# DK_ESC.net
KiCad netlist of a schematic drawn in EAGLE
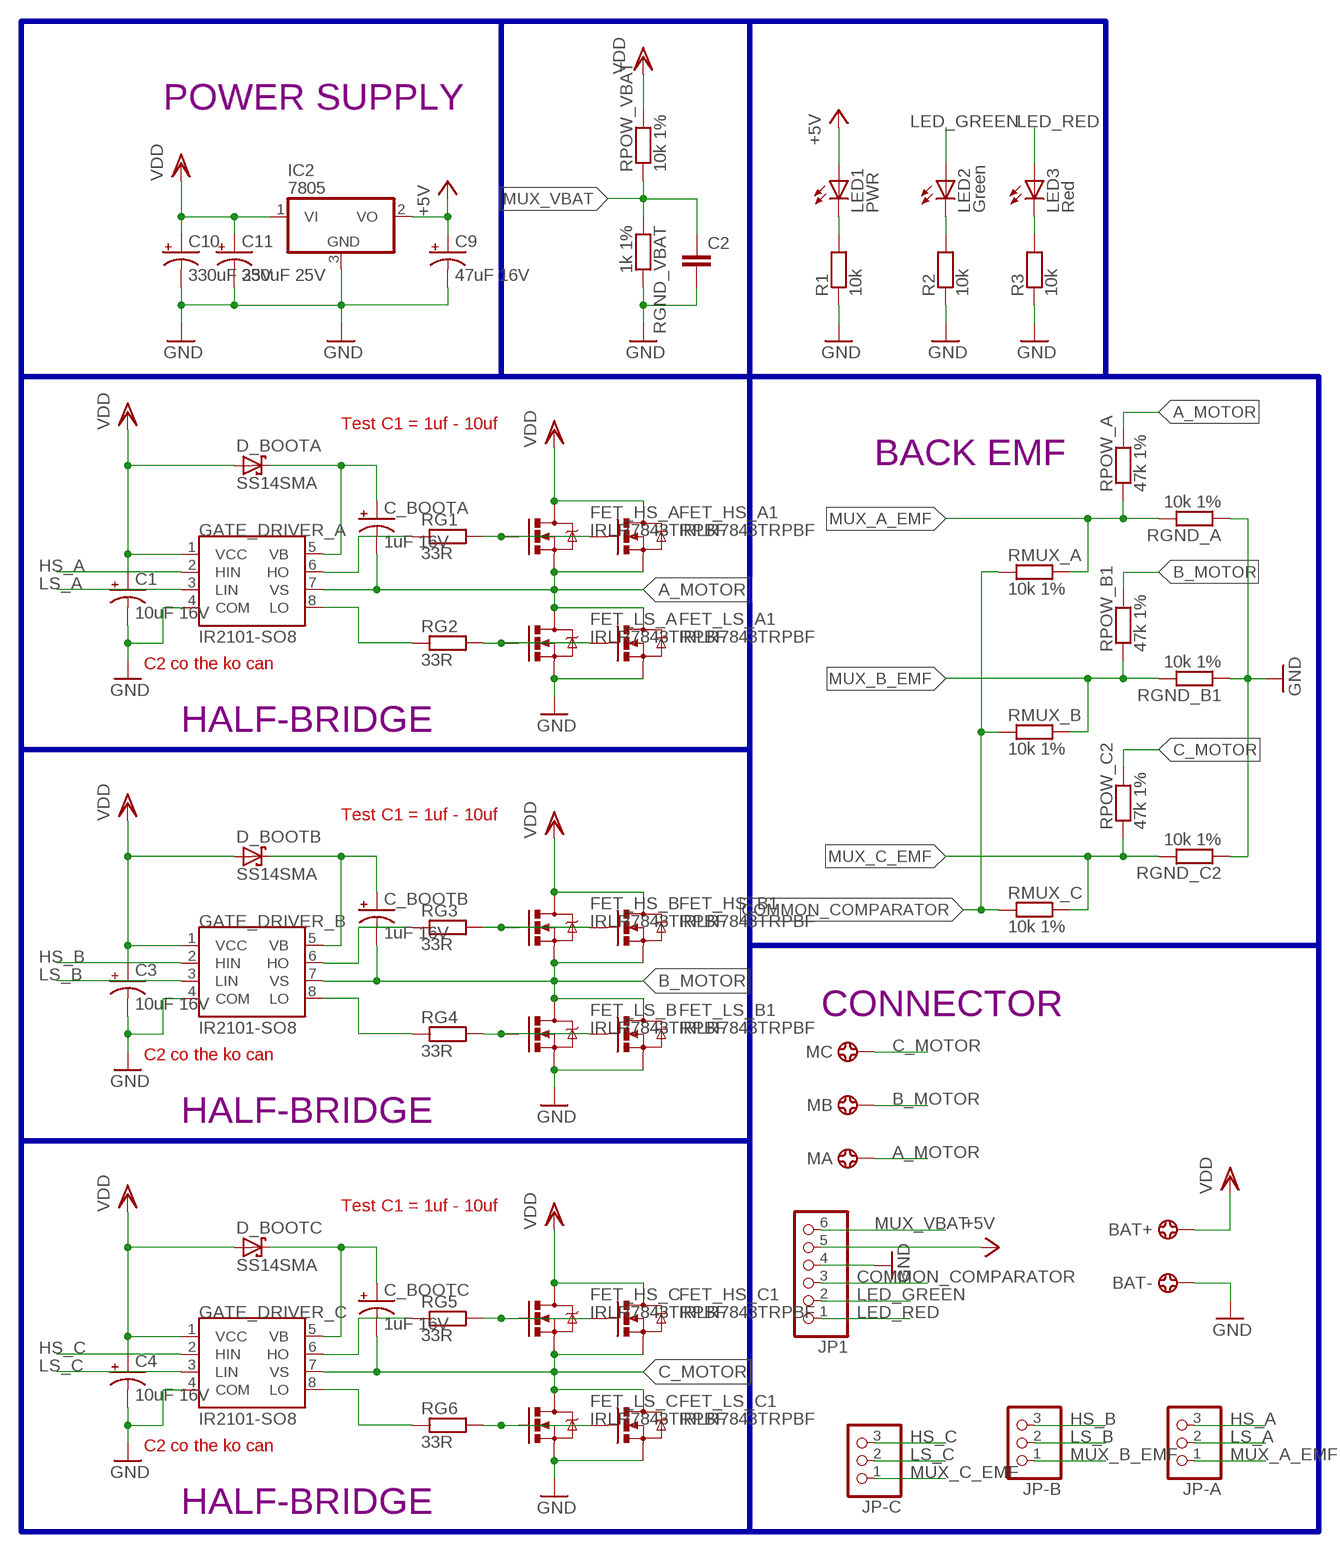
[diagram p0: schematic, sheet 1]

(export (version "E")
  (design (tool "Eeschema 10.0.6"))
  (components
    (comp (ref "BAT+")
      (value "14AWG_PAD-PAD")
      (footprint "eagle-import:14AWG")
      (libsource (lib "eagle-import") (part "14AWG_PAD-PAD"))
    )
    (comp (ref "BAT-")
      (value "14AWG_PAD-PAD")
      (footprint "eagle-import:14AWG")
      (libsource (lib "eagle-import") (part "14AWG_PAD-PAD"))
    )
    (comp (ref "C1")
      (value "10uF 16V")
      (footprint "eagle-import:EIA3216-KIT")
      (libsource (lib "eagle-import") (part "CAP_POL1206-KIT"))
    )
    (comp (ref "C2")
      (value "C-SMDC0805K")
      (footprint "eagle-import:C0805K")
      (libsource (lib "eagle-import") (part "C-SMDC0805K"))
    )
    (comp (ref "C3")
      (value "10uF 16V")
      (footprint "eagle-import:EIA3216-KIT")
      (libsource (lib "eagle-import") (part "CAP_POL1206-KIT"))
    )
    (comp (ref "C4")
      (value "10uF 16V")
      (footprint "eagle-import:EIA3216-KIT")
      (libsource (lib "eagle-import") (part "CAP_POL1206-KIT"))
    )
    (comp (ref "C9")
      (value "47uF 16V")
      (footprint "eagle-import:CT6032")
      (libsource (lib "eagle-import") (part "C-TANT-SMDEIA6032"))
    )
    (comp (ref "C10")
      (value "330uF 25V")
      (footprint "eagle-import:CPOL-PTH-330UF-16V")
      (libsource (lib "eagle-import") (part "CAP_POLPTH"))
    )
    (comp (ref "C11")
      (value "330uF 25V")
      (footprint "eagle-import:CPOL-PTH-330UF-16V")
      (libsource (lib "eagle-import") (part "CAP_POLPTH"))
    )
    (comp (ref "C_BOOTA")
      (value "1uF 16V")
      (footprint "eagle-import:EIA3216-KIT")
      (libsource (lib "eagle-import") (part "CAP_POL1206-KIT"))
    )
    (comp (ref "C_BOOTB")
      (value "1uF 16V")
      (footprint "eagle-import:EIA3216-KIT")
      (libsource (lib "eagle-import") (part "CAP_POL1206-KIT"))
    )
    (comp (ref "C_BOOTC")
      (value "1uF 16V")
      (footprint "eagle-import:EIA3216-KIT")
      (libsource (lib "eagle-import") (part "CAP_POL1206-KIT"))
    )
    (comp (ref "D_BOOTA")
      (value "SS14SMA")
      (footprint "eagle-import:DO214AC")
      (libsource (lib "eagle-import") (part "SS14SMA"))
    )
    (comp (ref "D_BOOTB")
      (value "SS14SMA")
      (footprint "eagle-import:DO214AC")
      (libsource (lib "eagle-import") (part "SS14SMA"))
    )
    (comp (ref "D_BOOTC")
      (value "SS14SMA")
      (footprint "eagle-import:DO214AC")
      (libsource (lib "eagle-import") (part "SS14SMA"))
    )
    (comp (ref "FET_HS_A")
      (value "IRLR7843TRPBF")
      (footprint "eagle-import:TO252")
      (libsource (lib "eagle-import") (part "IRLR7843TRPBF-DPAK"))
    )
    (comp (ref "FET_HS_A1")
      (value "IRLR7843TRPBF")
      (footprint "eagle-import:TO252")
      (libsource (lib "eagle-import") (part "IRLR7843TRPBF-DPAK"))
    )
    (comp (ref "FET_HS_B")
      (value "IRLR7843TRPBF")
      (footprint "eagle-import:TO252")
      (libsource (lib "eagle-import") (part "IRLR7843TRPBF-DPAK"))
    )
    (comp (ref "FET_HS_B1")
      (value "IRLR7843TRPBF")
      (footprint "eagle-import:TO252")
      (libsource (lib "eagle-import") (part "IRLR7843TRPBF-DPAK"))
    )
    (comp (ref "FET_HS_C")
      (value "IRLR7843TRPBF")
      (footprint "eagle-import:TO252")
      (libsource (lib "eagle-import") (part "IRLR7843TRPBF-DPAK"))
    )
    (comp (ref "FET_HS_C1")
      (value "IRLR7843TRPBF")
      (footprint "eagle-import:TO252")
      (libsource (lib "eagle-import") (part "IRLR7843TRPBF-DPAK"))
    )
    (comp (ref "FET_LS_A")
      (value "IRLR7843TRPBF")
      (footprint "eagle-import:TO252")
      (libsource (lib "eagle-import") (part "IRLR7843TRPBF-DPAK"))
    )
    (comp (ref "FET_LS_A1")
      (value "IRLR7843TRPBF")
      (footprint "eagle-import:TO252")
      (libsource (lib "eagle-import") (part "IRLR7843TRPBF-DPAK"))
    )
    (comp (ref "FET_LS_B")
      (value "IRLR7843TRPBF")
      (footprint "eagle-import:TO252")
      (libsource (lib "eagle-import") (part "IRLR7843TRPBF-DPAK"))
    )
    (comp (ref "FET_LS_B1")
      (value "IRLR7843TRPBF")
      (footprint "eagle-import:TO252")
      (libsource (lib "eagle-import") (part "IRLR7843TRPBF-DPAK"))
    )
    (comp (ref "FET_LS_C")
      (value "IRLR7843TRPBF")
      (footprint "eagle-import:TO252")
      (libsource (lib "eagle-import") (part "IRLR7843TRPBF-DPAK"))
    )
    (comp (ref "FET_LS_C1")
      (value "IRLR7843TRPBF")
      (footprint "eagle-import:TO252")
      (libsource (lib "eagle-import") (part "IRLR7843TRPBF-DPAK"))
    )
    (comp (ref "GATE_DRIVER_A")
      (value "IR2101-SO8")
      (footprint "eagle-import:SO08")
      (libsource (lib "eagle-import") (part "IR2101-SO8"))
    )
    (comp (ref "GATE_DRIVER_B")
      (value "IR2101-SO8")
      (footprint "eagle-import:SO08")
      (libsource (lib "eagle-import") (part "IR2101-SO8"))
    )
    (comp (ref "GATE_DRIVER_C")
      (value "IR2101-SO8")
      (footprint "eagle-import:SO08")
      (libsource (lib "eagle-import") (part "IR2101-SO8"))
    )
    (comp (ref "IC2")
      (value "7805")
      (footprint "eagle-import:TO252")
      (libsource (lib "eagle-import") (part "78XXX-3P-TO25205"))
    )
    (comp (ref "JP-A")
      (value "PINHD-1X3")
      (footprint "eagle-import:1X03")
      (libsource (lib "eagle-import") (part "PINHD-1X3"))
    )
    (comp (ref "JP-B")
      (value "PINHD-1X3")
      (footprint "eagle-import:1X03")
      (libsource (lib "eagle-import") (part "PINHD-1X3"))
    )
    (comp (ref "JP-C")
      (value "PINHD-1X3")
      (footprint "eagle-import:1X03")
      (libsource (lib "eagle-import") (part "PINHD-1X3"))
    )
    (comp (ref "JP1")
      (value "PINHD-1X6")
      (footprint "eagle-import:1X06")
      (libsource (lib "eagle-import") (part "PINHD-1X6"))
    )
    (comp (ref "LED1")
      (value "PWR")
      (footprint "eagle-import:LED_0805")
      (libsource (lib "eagle-import") (part "LED0805"))
    )
    (comp (ref "LED2")
      (value "Green")
      (footprint "eagle-import:LED_0805")
      (libsource (lib "eagle-import") (part "LED0805"))
    )
    (comp (ref "LED3")
      (value "Red")
      (footprint "eagle-import:LED_0805")
      (libsource (lib "eagle-import") (part "LED0805"))
    )
    (comp (ref "MA")
      (value "14AWG_PAD-PAD")
      (footprint "eagle-import:14AWG")
      (libsource (lib "eagle-import") (part "14AWG_PAD-PAD"))
    )
    (comp (ref "MB")
      (value "14AWG_PAD-PAD")
      (footprint "eagle-import:14AWG")
      (libsource (lib "eagle-import") (part "14AWG_PAD-PAD"))
    )
    (comp (ref "MC")
      (value "14AWG_PAD-PAD")
      (footprint "eagle-import:14AWG")
      (libsource (lib "eagle-import") (part "14AWG_PAD-PAD"))
    )
    (comp (ref "R1")
      (value "10k")
      (footprint "eagle-import:R0805")
      (libsource (lib "eagle-import") (part "RESISTOR-SMDR0805"))
    )
    (comp (ref "R2")
      (value "10k")
      (footprint "eagle-import:R0805")
      (libsource (lib "eagle-import") (part "RESISTOR-SMDR0805"))
    )
    (comp (ref "R3")
      (value "10k")
      (footprint "eagle-import:R0805")
      (libsource (lib "eagle-import") (part "RESISTOR-SMDR0805"))
    )
    (comp (ref "RG1")
      (value "33R")
      (footprint "eagle-import:R0603")
      (libsource (lib "eagle-import") (part "RESISTOR-SMDR0603"))
    )
    (comp (ref "RG2")
      (value "33R")
      (footprint "eagle-import:R0603")
      (libsource (lib "eagle-import") (part "RESISTOR-SMDR0603"))
    )
    (comp (ref "RG3")
      (value "33R")
      (footprint "eagle-import:R0603")
      (libsource (lib "eagle-import") (part "RESISTOR-SMDR0603"))
    )
    (comp (ref "RG4")
      (value "33R")
      (footprint "eagle-import:R0603")
      (libsource (lib "eagle-import") (part "RESISTOR-SMDR0603"))
    )
    (comp (ref "RG5")
      (value "33R")
      (footprint "eagle-import:R0603")
      (libsource (lib "eagle-import") (part "RESISTOR-SMDR0603"))
    )
    (comp (ref "RG6")
      (value "33R")
      (footprint "eagle-import:R0603")
      (libsource (lib "eagle-import") (part "RESISTOR-SMDR0603"))
    )
    (comp (ref "RGND_A")
      (value "10k 1%")
      (footprint "eagle-import:R0805")
      (libsource (lib "eagle-import") (part "RESISTOR-SMDR0805"))
    )
    (comp (ref "RGND_B1")
      (value "10k 1%")
      (footprint "eagle-import:R0805")
      (libsource (lib "eagle-import") (part "RESISTOR-SMDR0805"))
    )
    (comp (ref "RGND_C2")
      (value "10k 1%")
      (footprint "eagle-import:R0805")
      (libsource (lib "eagle-import") (part "RESISTOR-SMDR0805"))
    )
    (comp (ref "RGND_VBAT")
      (value "1k 1%")
      (footprint "eagle-import:R0805")
      (libsource (lib "eagle-import") (part "RESISTOR-SMDR0805"))
    )
    (comp (ref "RMUX_A")
      (value "10k 1%")
      (footprint "eagle-import:R0805")
      (libsource (lib "eagle-import") (part "RESISTOR-SMDR0805"))
    )
    (comp (ref "RMUX_B")
      (value "10k 1%")
      (footprint "eagle-import:R0805")
      (libsource (lib "eagle-import") (part "RESISTOR-SMDR0805"))
    )
    (comp (ref "RMUX_C")
      (value "10k 1%")
      (footprint "eagle-import:R0805")
      (libsource (lib "eagle-import") (part "RESISTOR-SMDR0805"))
    )
    (comp (ref "RPOW_A")
      (value "47k 1%")
      (footprint "eagle-import:R0603")
      (libsource (lib "eagle-import") (part "RESISTOR-SMDR0603"))
    )
    (comp (ref "RPOW_B1")
      (value "47k 1%")
      (footprint "eagle-import:R0603")
      (libsource (lib "eagle-import") (part "RESISTOR-SMDR0603"))
    )
    (comp (ref "RPOW_C2")
      (value "47k 1%")
      (footprint "eagle-import:R0603")
      (libsource (lib "eagle-import") (part "RESISTOR-SMDR0603"))
    )
    (comp (ref "RPOW_VBAT")
      (value "10k 1%")
      (footprint "eagle-import:R0805")
      (libsource (lib "eagle-import") (part "RESISTOR-SMDR0805"))
    )
  )
  (nets
    (net (code "1") (name "+5V") (class "Default")
      (node (ref "C9") (pin "+") (pinfunction "+_+") (pintype "passive"))
      (node (ref "IC2") (pin "2") (pinfunction "VO_2") (pintype "passive"))
      (node (ref "JP1") (pin "5") (pinfunction "5_5") (pintype "passive"))
      (node (ref "LED1") (pin "A") (pinfunction "A_A") (pintype "passive"))
    )
    (net (code "2") (name "/HS_A") (class "Default")
      (node (ref "GATE_DRIVER_A") (pin "2") (pinfunction "HIN_2") (pintype "input"))
      (node (ref "JP-A") (pin "3") (pinfunction "3_3") (pintype "passive"))
    )
    (net (code "3") (name "/HS_B") (class "Default")
      (node (ref "GATE_DRIVER_B") (pin "2") (pinfunction "HIN_2") (pintype "input"))
      (node (ref "JP-B") (pin "3") (pinfunction "3_3") (pintype "passive"))
    )
    (net (code "4") (name "/HS_C") (class "Default")
      (node (ref "GATE_DRIVER_C") (pin "2") (pinfunction "HIN_2") (pintype "input"))
      (node (ref "JP-C") (pin "3") (pinfunction "3_3") (pintype "passive"))
    )
    (net (code "5") (name "/LED_GREEN") (class "Default")
      (node (ref "JP1") (pin "2") (pinfunction "2_2") (pintype "passive"))
      (node (ref "LED2") (pin "A") (pinfunction "A_A") (pintype "passive"))
    )
    (net (code "6") (name "/LED_RED") (class "Default")
      (node (ref "JP1") (pin "1") (pinfunction "1_1") (pintype "passive"))
      (node (ref "LED3") (pin "A") (pinfunction "A_A") (pintype "passive"))
    )
    (net (code "7") (name "/LS_A") (class "Default")
      (node (ref "GATE_DRIVER_A") (pin "3") (pinfunction "LIN_3") (pintype "input"))
      (node (ref "JP-A") (pin "2") (pinfunction "2_2") (pintype "passive"))
    )
    (net (code "8") (name "/LS_B") (class "Default")
      (node (ref "GATE_DRIVER_B") (pin "3") (pinfunction "LIN_3") (pintype "input"))
      (node (ref "JP-B") (pin "2") (pinfunction "2_2") (pintype "passive"))
    )
    (net (code "9") (name "/LS_C") (class "Default")
      (node (ref "GATE_DRIVER_C") (pin "3") (pinfunction "LIN_3") (pintype "input"))
      (node (ref "JP-C") (pin "2") (pinfunction "2_2") (pintype "passive"))
    )
    (net (code "10") (name "/VB") (class "Default")
      (node (ref "C_BOOTA") (pin "A") (pinfunction "+_A") (pintype "passive"))
      (node (ref "C_BOOTB") (pin "A") (pinfunction "+_A") (pintype "passive"))
      (node (ref "C_BOOTC") (pin "A") (pinfunction "+_A") (pintype "passive"))
      (node (ref "D_BOOTA") (pin "C") (pinfunction "C_C") (pintype "passive"))
      (node (ref "D_BOOTB") (pin "C") (pinfunction "C_C") (pintype "passive"))
      (node (ref "D_BOOTC") (pin "C") (pinfunction "C_C") (pintype "passive"))
      (node (ref "GATE_DRIVER_A") (pin "5") (pinfunction "VB_5") (pintype "power_in"))
      (node (ref "GATE_DRIVER_B") (pin "5") (pinfunction "VB_5") (pintype "power_in"))
      (node (ref "GATE_DRIVER_C") (pin "5") (pinfunction "VB_5") (pintype "power_in"))
    )
    (net (code "11") (name "A_MOTOR") (class "Default")
      (node (ref "C_BOOTA") (pin "C") (pinfunction "-_C") (pintype "passive"))
      (node (ref "FET_HS_A") (pin "3") (pinfunction "S_3") (pintype "passive"))
      (node (ref "FET_HS_A1") (pin "3") (pinfunction "S_3") (pintype "passive"))
      (node (ref "FET_LS_A") (pin "2") (pinfunction "D_2") (pintype "passive"))
      (node (ref "FET_LS_A1") (pin "2") (pinfunction "D_2") (pintype "passive"))
      (node (ref "GATE_DRIVER_A") (pin "7") (pinfunction "VS_7") (pintype "output"))
      (node (ref "MA") (pin "1") (pinfunction "1_1") (pintype "passive"))
      (node (ref "RPOW_A") (pin "2") (pinfunction "2_2") (pintype "passive"))
    )
    (net (code "12") (name "B_MOTOR") (class "Default")
      (node (ref "C_BOOTB") (pin "C") (pinfunction "-_C") (pintype "passive"))
      (node (ref "FET_HS_B") (pin "3") (pinfunction "S_3") (pintype "passive"))
      (node (ref "FET_HS_B1") (pin "3") (pinfunction "S_3") (pintype "passive"))
      (node (ref "FET_LS_B") (pin "2") (pinfunction "D_2") (pintype "passive"))
      (node (ref "FET_LS_B1") (pin "2") (pinfunction "D_2") (pintype "passive"))
      (node (ref "GATE_DRIVER_B") (pin "7") (pinfunction "VS_7") (pintype "output"))
      (node (ref "MB") (pin "1") (pinfunction "1_1") (pintype "passive"))
      (node (ref "RPOW_B1") (pin "2") (pinfunction "2_2") (pintype "passive"))
    )
    (net (code "13") (name "COMMON_COMPARATOR") (class "Default")
      (node (ref "JP1") (pin "3") (pinfunction "3_3") (pintype "passive"))
      (node (ref "RMUX_A") (pin "1") (pinfunction "1_1") (pintype "passive"))
      (node (ref "RMUX_B") (pin "1") (pinfunction "1_1") (pintype "passive"))
      (node (ref "RMUX_C") (pin "1") (pinfunction "1_1") (pintype "passive"))
    )
    (net (code "14") (name "C_MOTOR") (class "Default")
      (node (ref "C_BOOTC") (pin "C") (pinfunction "-_C") (pintype "passive"))
      (node (ref "FET_HS_C") (pin "3") (pinfunction "S_3") (pintype "passive"))
      (node (ref "FET_HS_C1") (pin "3") (pinfunction "S_3") (pintype "passive"))
      (node (ref "FET_LS_C") (pin "2") (pinfunction "D_2") (pintype "passive"))
      (node (ref "FET_LS_C1") (pin "2") (pinfunction "D_2") (pintype "passive"))
      (node (ref "GATE_DRIVER_C") (pin "7") (pinfunction "VS_7") (pintype "output"))
      (node (ref "MC") (pin "1") (pinfunction "1_1") (pintype "passive"))
      (node (ref "RPOW_C2") (pin "2") (pinfunction "2_2") (pintype "passive"))
    )
    (net (code "15") (name "GND") (class "Default")
      (node (ref "BAT-") (pin "1") (pinfunction "1_1") (pintype "passive"))
      (node (ref "C1") (pin "C") (pinfunction "-_C") (pintype "passive"))
      (node (ref "C10") (pin "-") (pinfunction "-_-") (pintype "passive"))
      (node (ref "C11") (pin "-") (pinfunction "-_-") (pintype "passive"))
      (node (ref "C2") (pin "2") (pinfunction "2_2") (pintype "passive"))
      (node (ref "C3") (pin "C") (pinfunction "-_C") (pintype "passive"))
      (node (ref "C4") (pin "C") (pinfunction "-_C") (pintype "passive"))
      (node (ref "C9") (pin "-") (pinfunction "-_-") (pintype "passive"))
      (node (ref "FET_LS_A") (pin "3") (pinfunction "S_3") (pintype "passive"))
      (node (ref "FET_LS_A1") (pin "3") (pinfunction "S_3") (pintype "passive"))
      (node (ref "FET_LS_B") (pin "3") (pinfunction "S_3") (pintype "passive"))
      (node (ref "FET_LS_B1") (pin "3") (pinfunction "S_3") (pintype "passive"))
      (node (ref "FET_LS_C") (pin "3") (pinfunction "S_3") (pintype "passive"))
      (node (ref "FET_LS_C1") (pin "3") (pinfunction "S_3") (pintype "passive"))
      (node (ref "GATE_DRIVER_A") (pin "4") (pinfunction "COM_4") (pintype "power_in"))
      (node (ref "GATE_DRIVER_B") (pin "4") (pinfunction "COM_4") (pintype "power_in"))
      (node (ref "GATE_DRIVER_C") (pin "4") (pinfunction "COM_4") (pintype "power_in"))
      (node (ref "IC2") (pin "3") (pinfunction "GND_3") (pintype "passive"))
      (node (ref "JP1") (pin "4") (pinfunction "4_4") (pintype "passive"))
      (node (ref "R1") (pin "1") (pinfunction "1_1") (pintype "passive"))
      (node (ref "R2") (pin "1") (pinfunction "1_1") (pintype "passive"))
      (node (ref "R3") (pin "1") (pinfunction "1_1") (pintype "passive"))
      (node (ref "RGND_A") (pin "1") (pinfunction "1_1") (pintype "passive"))
      (node (ref "RGND_B1") (pin "1") (pinfunction "1_1") (pintype "passive"))
      (node (ref "RGND_C2") (pin "1") (pinfunction "1_1") (pintype "passive"))
      (node (ref "RGND_VBAT") (pin "2") (pinfunction "2_2") (pintype "passive"))
    )
    (net (code "16") (name "MUX_A_EMF") (class "Default")
      (node (ref "JP-A") (pin "1") (pinfunction "1_1") (pintype "passive"))
      (node (ref "RGND_A") (pin "2") (pinfunction "2_2") (pintype "passive"))
      (node (ref "RMUX_A") (pin "2") (pinfunction "2_2") (pintype "passive"))
      (node (ref "RPOW_A") (pin "1") (pinfunction "1_1") (pintype "passive"))
    )
    (net (code "17") (name "MUX_B_EMF") (class "Default")
      (node (ref "JP-B") (pin "1") (pinfunction "1_1") (pintype "passive"))
      (node (ref "RGND_B1") (pin "2") (pinfunction "2_2") (pintype "passive"))
      (node (ref "RMUX_B") (pin "2") (pinfunction "2_2") (pintype "passive"))
      (node (ref "RPOW_B1") (pin "1") (pinfunction "1_1") (pintype "passive"))
    )
    (net (code "18") (name "MUX_C_EMF") (class "Default")
      (node (ref "JP-C") (pin "1") (pinfunction "1_1") (pintype "passive"))
      (node (ref "RGND_C2") (pin "2") (pinfunction "2_2") (pintype "passive"))
      (node (ref "RMUX_C") (pin "2") (pinfunction "2_2") (pintype "passive"))
      (node (ref "RPOW_C2") (pin "1") (pinfunction "1_1") (pintype "passive"))
    )
    (net (code "19") (name "MUX_VBAT") (class "Default")
      (node (ref "C2") (pin "1") (pinfunction "1_1") (pintype "passive"))
      (node (ref "JP1") (pin "6") (pinfunction "6_6") (pintype "passive"))
      (node (ref "RGND_VBAT") (pin "1") (pinfunction "1_1") (pintype "passive"))
      (node (ref "RPOW_VBAT") (pin "1") (pinfunction "1_1") (pintype "passive"))
    )
    (net (code "20") (name "Net-(FET_HS_A-G)") (class "Default")
      (node (ref "FET_HS_A") (pin "1") (pinfunction "G_1") (pintype "passive"))
      (node (ref "FET_HS_A1") (pin "1") (pinfunction "G_1") (pintype "passive"))
      (node (ref "RG1") (pin "2") (pinfunction "2_2") (pintype "passive"))
    )
    (net (code "21") (name "Net-(FET_HS_B-G)") (class "Default")
      (node (ref "FET_HS_B") (pin "1") (pinfunction "G_1") (pintype "passive"))
      (node (ref "FET_HS_B1") (pin "1") (pinfunction "G_1") (pintype "passive"))
      (node (ref "RG3") (pin "2") (pinfunction "2_2") (pintype "passive"))
    )
    (net (code "22") (name "Net-(FET_HS_C-G)") (class "Default")
      (node (ref "FET_HS_C") (pin "1") (pinfunction "G_1") (pintype "passive"))
      (node (ref "FET_HS_C1") (pin "1") (pinfunction "G_1") (pintype "passive"))
      (node (ref "RG5") (pin "2") (pinfunction "2_2") (pintype "passive"))
    )
    (net (code "23") (name "Net-(FET_LS_A-G)") (class "Default")
      (node (ref "FET_LS_A") (pin "1") (pinfunction "G_1") (pintype "passive"))
      (node (ref "FET_LS_A1") (pin "1") (pinfunction "G_1") (pintype "passive"))
      (node (ref "RG2") (pin "2") (pinfunction "2_2") (pintype "passive"))
    )
    (net (code "24") (name "Net-(FET_LS_B-G)") (class "Default")
      (node (ref "FET_LS_B") (pin "1") (pinfunction "G_1") (pintype "passive"))
      (node (ref "FET_LS_B1") (pin "1") (pinfunction "G_1") (pintype "passive"))
      (node (ref "RG4") (pin "2") (pinfunction "2_2") (pintype "passive"))
    )
    (net (code "25") (name "Net-(FET_LS_C-G)") (class "Default")
      (node (ref "FET_LS_C") (pin "1") (pinfunction "G_1") (pintype "passive"))
      (node (ref "FET_LS_C1") (pin "1") (pinfunction "G_1") (pintype "passive"))
      (node (ref "RG6") (pin "2") (pinfunction "2_2") (pintype "passive"))
    )
    (net (code "26") (name "Net-(GATE_DRIVER_A-HO)") (class "Default")
      (node (ref "GATE_DRIVER_A") (pin "6") (pinfunction "HO_6") (pintype "output"))
      (node (ref "RG1") (pin "1") (pinfunction "1_1") (pintype "passive"))
    )
    (net (code "27") (name "Net-(GATE_DRIVER_A-LO)") (class "Default")
      (node (ref "GATE_DRIVER_A") (pin "8") (pinfunction "LO_8") (pintype "output"))
      (node (ref "RG2") (pin "1") (pinfunction "1_1") (pintype "passive"))
    )
    (net (code "28") (name "Net-(GATE_DRIVER_B-HO)") (class "Default")
      (node (ref "GATE_DRIVER_B") (pin "6") (pinfunction "HO_6") (pintype "output"))
      (node (ref "RG3") (pin "1") (pinfunction "1_1") (pintype "passive"))
    )
    (net (code "29") (name "Net-(GATE_DRIVER_B-LO)") (class "Default")
      (node (ref "GATE_DRIVER_B") (pin "8") (pinfunction "LO_8") (pintype "output"))
      (node (ref "RG4") (pin "1") (pinfunction "1_1") (pintype "passive"))
    )
    (net (code "30") (name "Net-(GATE_DRIVER_C-HO)") (class "Default")
      (node (ref "GATE_DRIVER_C") (pin "6") (pinfunction "HO_6") (pintype "output"))
      (node (ref "RG5") (pin "1") (pinfunction "1_1") (pintype "passive"))
    )
    (net (code "31") (name "Net-(GATE_DRIVER_C-LO)") (class "Default")
      (node (ref "GATE_DRIVER_C") (pin "8") (pinfunction "LO_8") (pintype "output"))
      (node (ref "RG6") (pin "1") (pinfunction "1_1") (pintype "passive"))
    )
    (net (code "32") (name "Net-(LED1-PadC)") (class "Default")
      (node (ref "LED1") (pin "C") (pinfunction "C_C") (pintype "passive"))
      (node (ref "R1") (pin "2") (pinfunction "2_2") (pintype "passive"))
    )
    (net (code "33") (name "Net-(LED2-PadC)") (class "Default")
      (node (ref "LED2") (pin "C") (pinfunction "C_C") (pintype "passive"))
      (node (ref "R2") (pin "2") (pinfunction "2_2") (pintype "passive"))
    )
    (net (code "34") (name "Net-(LED3-PadC)") (class "Default")
      (node (ref "LED3") (pin "C") (pinfunction "C_C") (pintype "passive"))
      (node (ref "R3") (pin "2") (pinfunction "2_2") (pintype "passive"))
    )
    (net (code "35") (name "VDD") (class "Default")
      (node (ref "BAT+") (pin "1") (pinfunction "1_1") (pintype "passive"))
      (node (ref "C1") (pin "A") (pinfunction "+_A") (pintype "passive"))
      (node (ref "C10") (pin "+") (pinfunction "+_+") (pintype "passive"))
      (node (ref "C11") (pin "+") (pinfunction "+_+") (pintype "passive"))
      (node (ref "C3") (pin "A") (pinfunction "+_A") (pintype "passive"))
      (node (ref "C4") (pin "A") (pinfunction "+_A") (pintype "passive"))
      (node (ref "D_BOOTA") (pin "A") (pinfunction "A_A") (pintype "passive"))
      (node (ref "D_BOOTB") (pin "A") (pinfunction "A_A") (pintype "passive"))
      (node (ref "D_BOOTC") (pin "A") (pinfunction "A_A") (pintype "passive"))
      (node (ref "FET_HS_A") (pin "2") (pinfunction "D_2") (pintype "passive"))
      (node (ref "FET_HS_A1") (pin "2") (pinfunction "D_2") (pintype "passive"))
      (node (ref "FET_HS_B") (pin "2") (pinfunction "D_2") (pintype "passive"))
      (node (ref "FET_HS_B1") (pin "2") (pinfunction "D_2") (pintype "passive"))
      (node (ref "FET_HS_C") (pin "2") (pinfunction "D_2") (pintype "passive"))
      (node (ref "FET_HS_C1") (pin "2") (pinfunction "D_2") (pintype "passive"))
      (node (ref "GATE_DRIVER_A") (pin "1") (pinfunction "VCC_1") (pintype "power_in"))
      (node (ref "GATE_DRIVER_B") (pin "1") (pinfunction "VCC_1") (pintype "power_in"))
      (node (ref "GATE_DRIVER_C") (pin "1") (pinfunction "VCC_1") (pintype "power_in"))
      (node (ref "IC2") (pin "1") (pinfunction "VI_1") (pintype "input"))
      (node (ref "RPOW_VBAT") (pin "2") (pinfunction "2_2") (pintype "passive"))
    )
  )
)
